# SIMM800C-STM32F103C8T6.net
KiCad netlist of a schematic drawn in Altium Designer
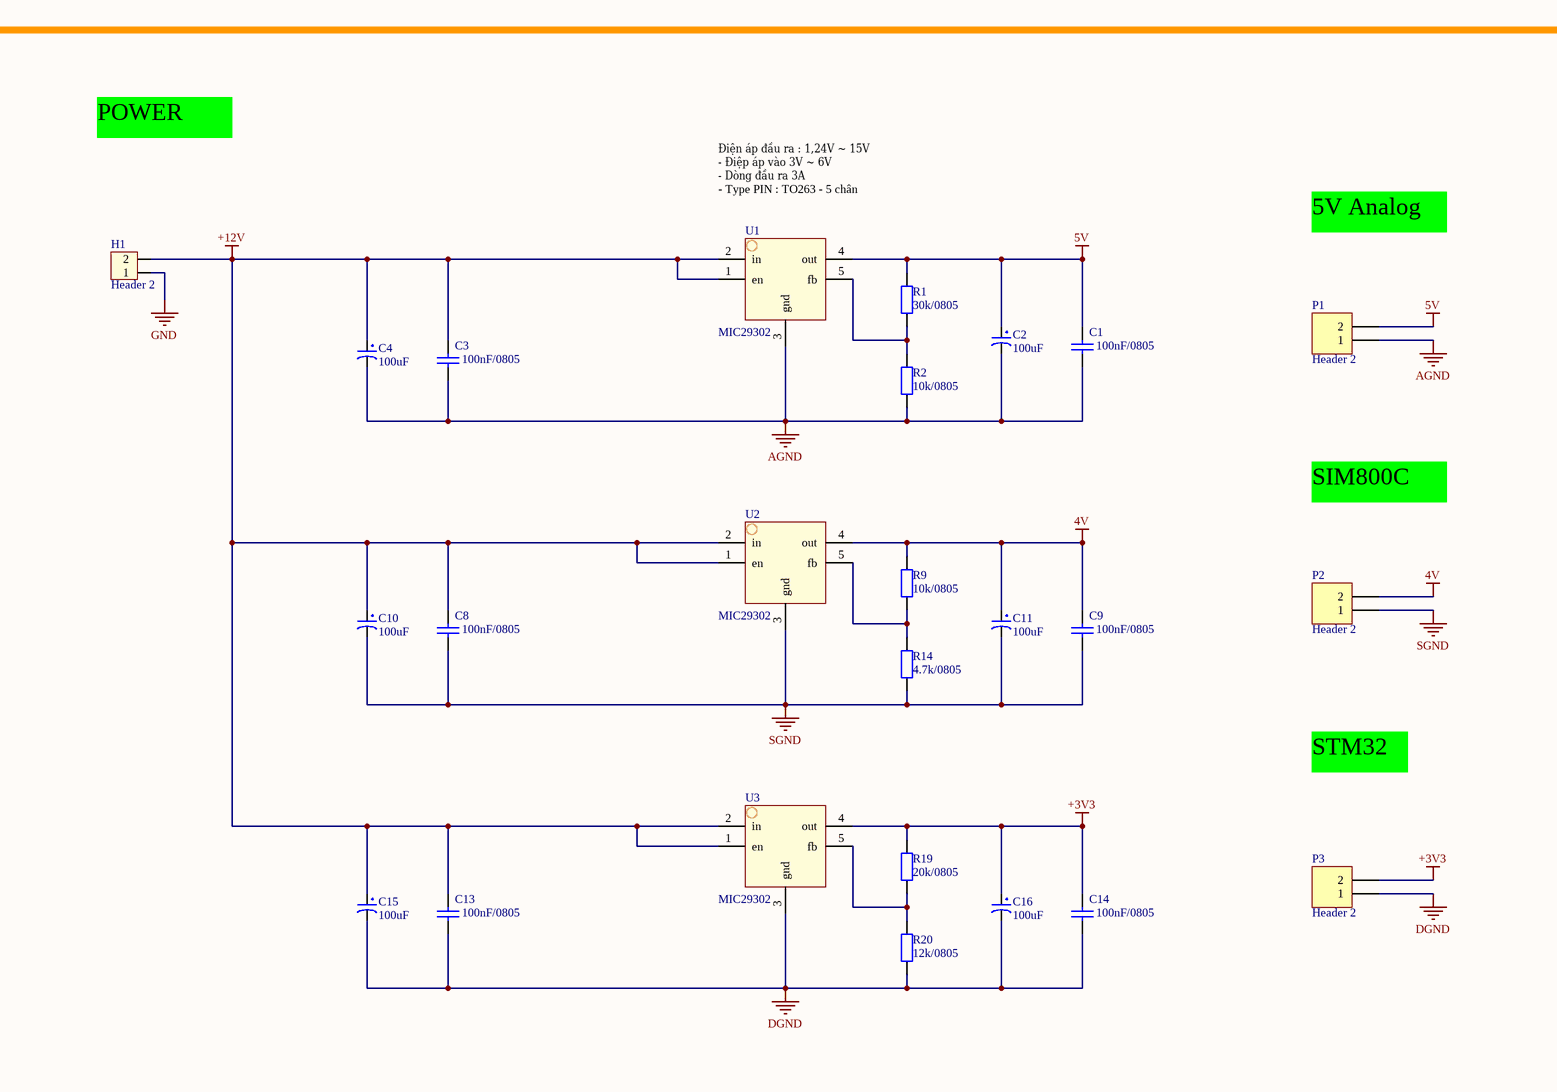
[diagram p0: SIMM800C-STM32F103C8T6.SchDoc, top left]
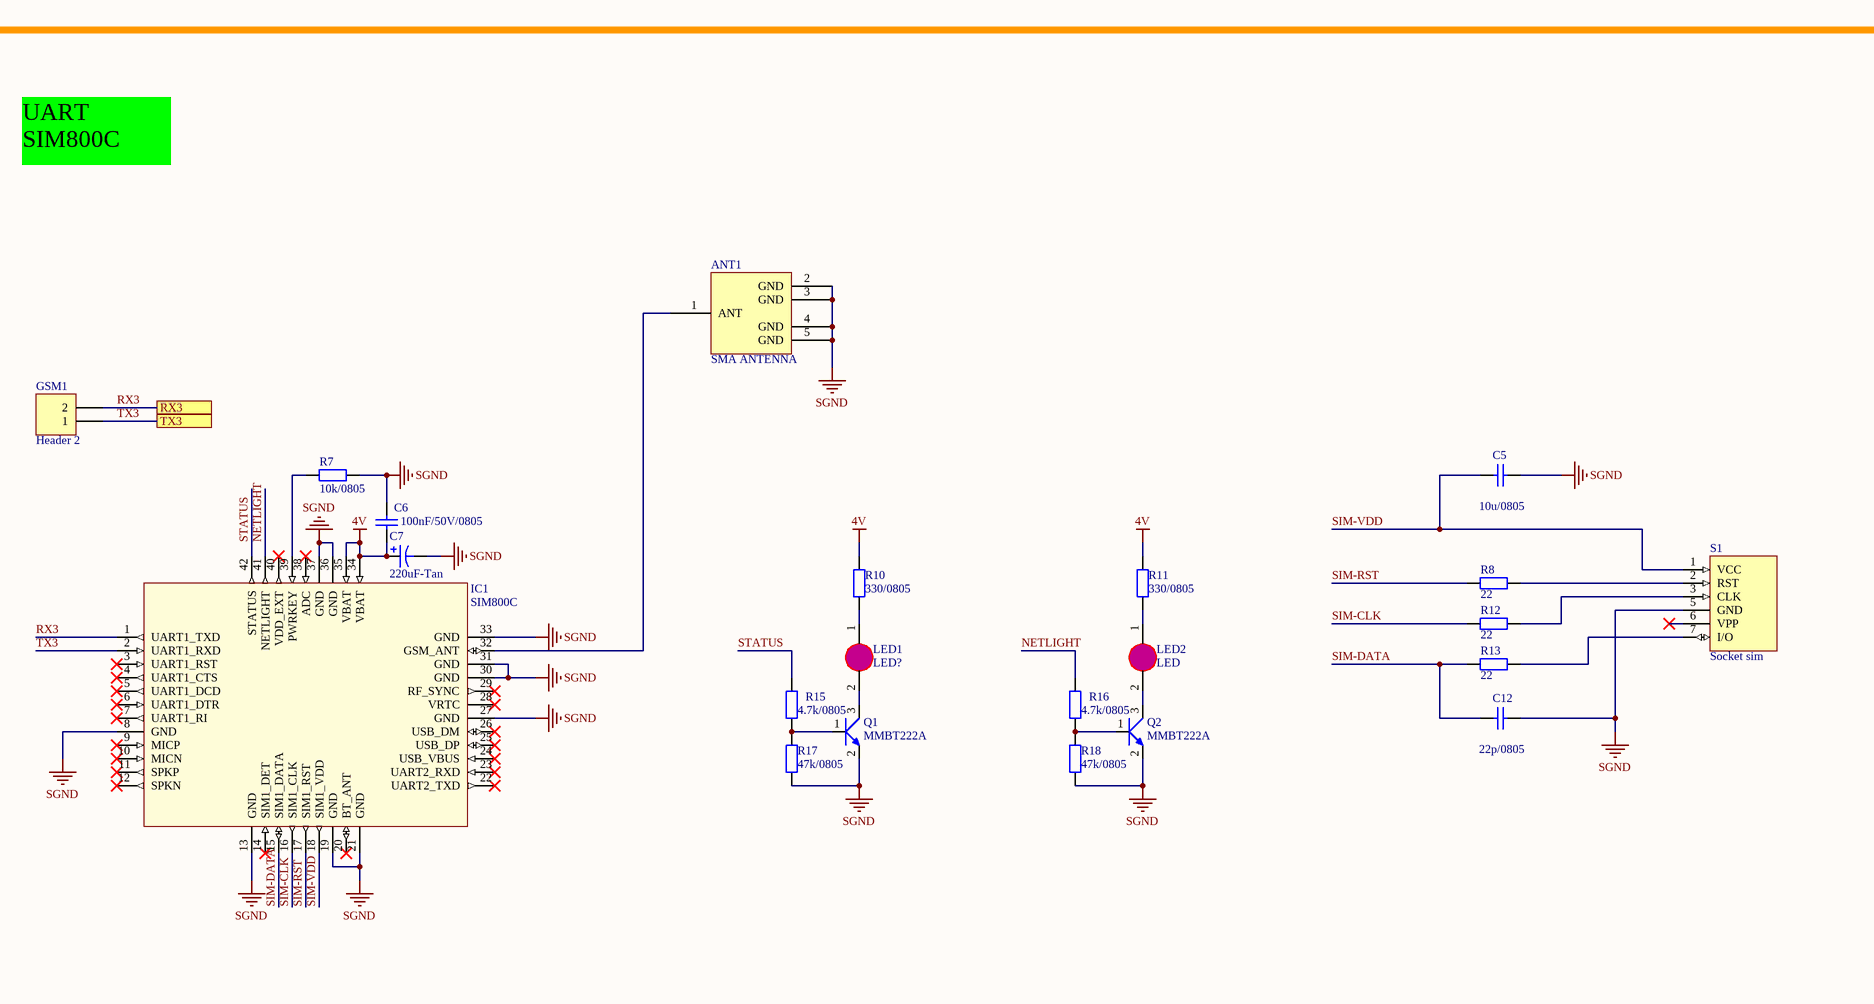
[diagram p1: SIMM800C-STM32F103C8T6.SchDoc, top right]
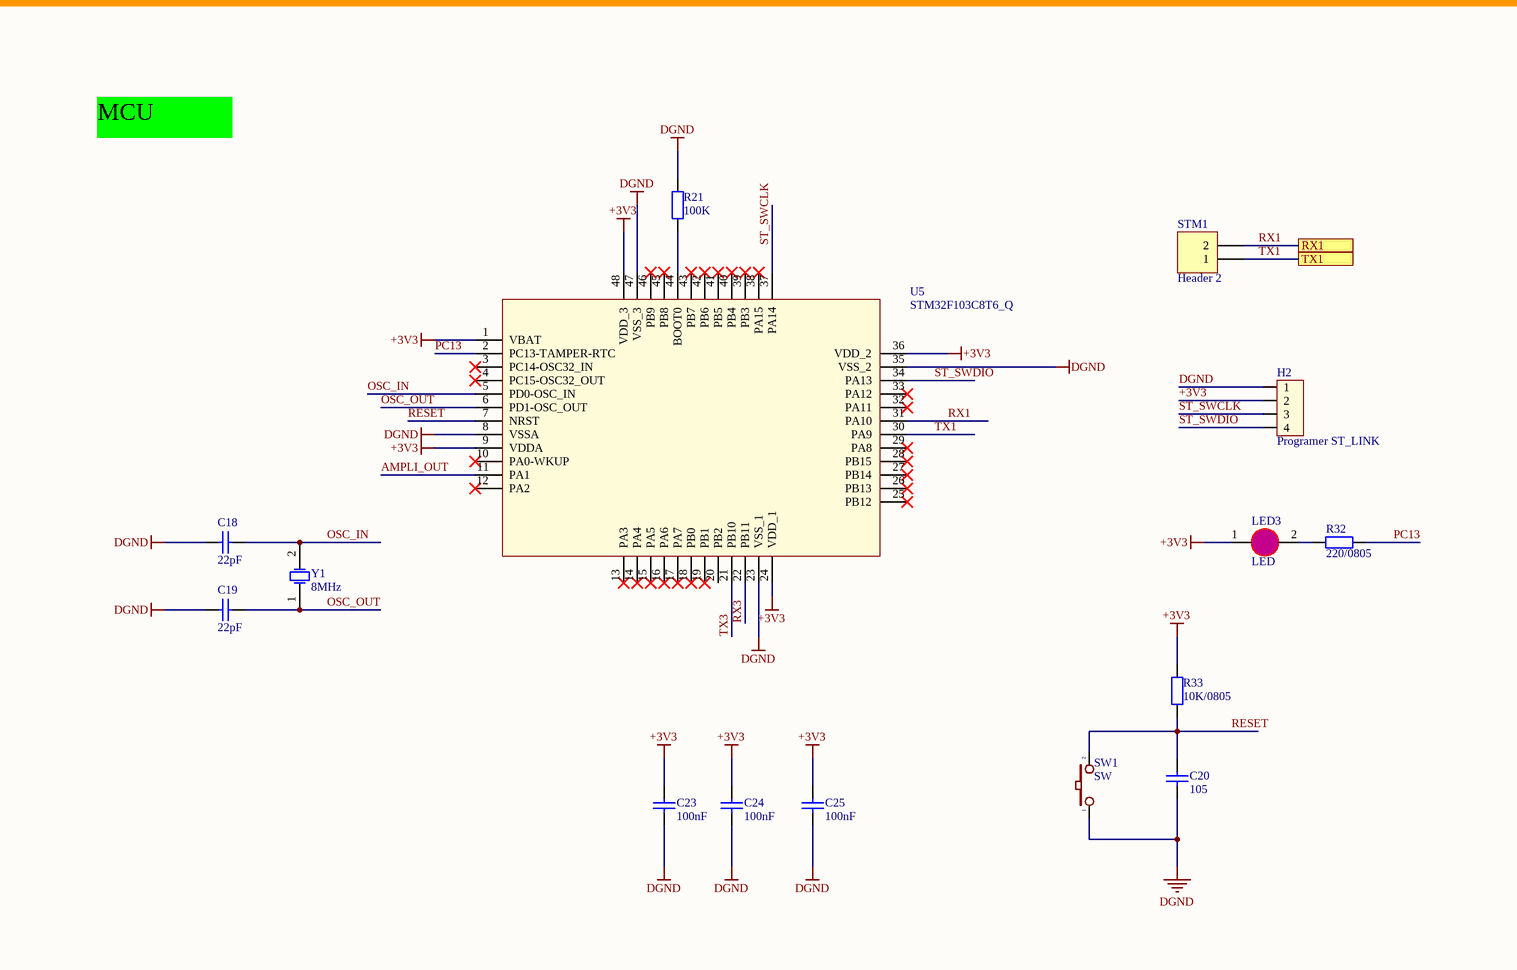
[diagram p2: SIMM800C-STM32F103C8T6.SchDoc, bottom left]
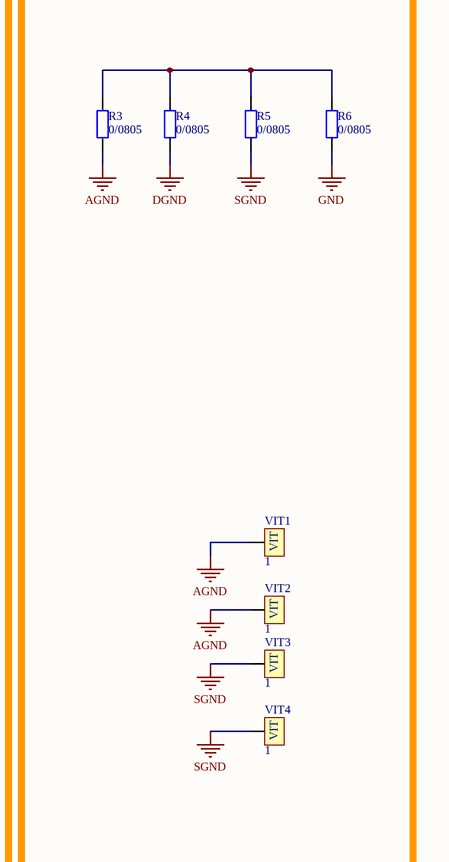
[diagram p3: SIMM800C-STM32F103C8T6.SchDoc, bottom right]

(export (version "E")
  (design (tool "Eeschema 10.0.6"))
  (components
    (comp (ref "ANT1")
      (value "SMA ANTENNA")
      (footprint "du an mau 1:ANT-SMA-ST-F")
      (libsource (lib "Air_System_lib") (part "SMA ANTENNA"))
    )
    (comp (ref "C1")
      (value "100nF/0805")
      (footprint "C0805-2012")
      (description "100nF/50V/0805")
      (fields (field (name "PUBLISHER") "Altium Limited"))
      (libsource (lib "NBBLib 14-03-2012") (part "CapSMD"))
    )
    (comp (ref "C2")
      (value "100uF")
      (footprint "CAP_TANTA_10UF_35V")
      (description "Cap 100uF/35V - 470uF/16V")
      (libsource (lib "lpson") (part "CP3"))
    )
    (comp (ref "C3")
      (value "100nF/0805")
      (footprint "C0805-2012")
      (description "100nF/50V/0805")
      (fields (field (name "PUBLISHER") "Altium Limited"))
      (libsource (lib "NBBLib 14-03-2012") (part "CapSMD"))
    )
    (comp (ref "C4")
      (value "100uF")
      (footprint "CAP_TANTA_10UF_35V")
      (description "Cap 100uF/35V - 470uF/16V")
      (libsource (lib "lpson") (part "CP3"))
    )
    (comp (ref "C5")
      (value "10u/0805")
      (footprint "C0805-2012")
      (description "Capacitor")
      (fields (field (name "PUBLISHER") "Altium Limited"))
      (libsource (lib "NBBLib 14-03-2012") (part "CapSMD"))
    )
    (comp (ref "C6")
      (value "100nF/50V/0805")
      (footprint "C0805-2012")
      (fields (field (name "PUBLISHER") "Altium Limited"))
      (libsource (lib "NBBLib 14-03-2012") (part "CapSMD"))
    )
    (comp (ref "C7")
      (value "220uF-Tan")
      (footprint "CAP_TANTA_10UF_35V")
      (libsource (lib "Air_System_lib") (part "CAP1210-Tan"))
    )
    (comp (ref "C8")
      (value "100nF/0805")
      (footprint "C0805-2012")
      (description "100nF/50V/0805")
      (fields (field (name "PUBLISHER") "Altium Limited"))
      (libsource (lib "NBBLib 14-03-2012") (part "CapSMD"))
    )
    (comp (ref "C9")
      (value "100nF/0805")
      (footprint "C0805-2012")
      (description "100nF/50V/0805")
      (fields (field (name "PUBLISHER") "Altium Limited"))
      (libsource (lib "NBBLib 14-03-2012") (part "CapSMD"))
    )
    (comp (ref "C10")
      (value "100uF")
      (footprint "CAP_TANTA_10UF_35V")
      (description "Cap 100uF/35V - 470uF/16V")
      (libsource (lib "lpson") (part "CP3"))
    )
    (comp (ref "C11")
      (value "100uF")
      (footprint "CAP_TANTA_10UF_35V")
      (description "Cap 100uF/35V - 470uF/16V")
      (libsource (lib "lpson") (part "CP3"))
    )
    (comp (ref "C12")
      (value "22p/0805")
      (footprint "C0805-2012")
      (description "Capacitor")
      (fields (field (name "PUBLISHER") "Altium Limited"))
      (libsource (lib "NBBLib 14-03-2012") (part "CapSMD"))
    )
    (comp (ref "C13")
      (value "100nF/0805")
      (footprint "C0805-2012")
      (description "100nF/50V/0805")
      (fields (field (name "PUBLISHER") "Altium Limited"))
      (libsource (lib "NBBLib 14-03-2012") (part "CapSMD"))
    )
    (comp (ref "C14")
      (value "100nF/0805")
      (footprint "C0805-2012")
      (description "100nF/50V/0805")
      (fields (field (name "PUBLISHER") "Altium Limited"))
      (libsource (lib "NBBLib 14-03-2012") (part "CapSMD"))
    )
    (comp (ref "C15")
      (value "100uF")
      (footprint "CAP_TANTA_10UF_35V")
      (description "Cap 100uF/35V - 470uF/16V")
      (libsource (lib "lpson") (part "CP3"))
    )
    (comp (ref "C16")
      (value "100uF")
      (footprint "CAP_TANTA_10UF_35V")
      (description "Cap 100uF/35V - 470uF/16V")
      (libsource (lib "lpson") (part "CP3"))
    )
    (comp (ref "C18")
      (value "22pF")
      (footprint "C0805-2012")
      (description "Capacitor")
      (fields (field (name "Comment") "Cap") (field (name "PUBLISHER") "Altium Limited"))
      (libsource (lib "STLINKv2DIYmơi") (part "Cap"))
    )
    (comp (ref "C19")
      (value "22pF")
      (footprint "C0805-2012")
      (description "Capacitor")
      (fields (field (name "Comment") "Cap") (field (name "PUBLISHER") "Altium Limited"))
      (libsource (lib "STLINKv2DIYmơi") (part "Cap"))
    )
    (comp (ref "C20")
      (value "105")
      (footprint "C0805-2012")
      (description "Capacitor")
      (fields (field (name "Comment") "Cap") (field (name "PUBLISHER") "Altium Limited"))
      (libsource (lib "STLINKv2DIYmơi") (part "Cap"))
    )
    (comp (ref "C23")
      (value "100nF")
      (footprint "C0805-2012")
      (description "Capacitor")
      (fields (field (name "Comment") "Cap") (field (name "PUBLISHER") "Altium Limited"))
      (libsource (lib "STLINKv2DIYmơi") (part "Cap"))
    )
    (comp (ref "C24")
      (value "100nF")
      (footprint "C0805-2012")
      (description "Capacitor")
      (fields (field (name "Comment") "Cap") (field (name "PUBLISHER") "Altium Limited"))
      (libsource (lib "STLINKv2DIYmơi") (part "Cap"))
    )
    (comp (ref "C25")
      (value "100nF")
      (footprint "C0805-2012")
      (description "Capacitor")
      (fields (field (name "Comment") "Cap") (field (name "PUBLISHER") "Altium Limited"))
      (libsource (lib "STLINKv2DIYmơi") (part "Cap"))
    )
    (comp (ref "GSM1")
      (value "Header 2")
      (footprint "Header_2")
      (description "Header, 2-Pin")
      (fields (field (name "PUBLISHER") "Altium Limited"))
      (libsource (lib "NBBLib 14-03-2012") (part "Header 2"))
    )
    (comp (ref "H1")
      (value "Header 2")
      (footprint "DOMINO2_GREEN")
      (description "Header 2 (Green)")
      (libsource (lib "lpson") (part "Hed2"))
    )
    (comp (ref "H2")
      (value "Programer ST_LINK")
      (footprint "Header_4")
      (description "Header 4 (Green)")
      (libsource (lib "lpson") (part "Hed4"))
    )
    (comp (ref "IC1")
      (value "SIM800C")
      (footprint "SIM800C")
      (description "SIM800C V1.00")
      (libsource (lib "LIEMTHANH_LIB") (part "SIM800C"))
    )
    (comp (ref "LED1")
      (value "LED?")
      (footprint "Led 0805R")
      (description "LED SMD 0805")
      (libsource (lib "NBBLib 14-03-2012") (part "LED0805"))
    )
    (comp (ref "LED2")
      (value "LED")
      (footprint "Led 0805R")
      (description "LED SMD 0805")
      (libsource (lib "NBBLib 14-03-2012") (part "LED0805"))
    )
    (comp (ref "LED3")
      (value "LED")
      (footprint "Led 0805G")
      (description "LED SMD 0805")
      (libsource (lib "NBBLib 14-03-2012") (part "LED0805"))
    )
    (comp (ref "P1")
      (value "Header 2")
      (footprint "Header_2")
      (description "Header, 2-Pin")
      (fields (field (name "PUBLISHER") "Altium Limited"))
      (libsource (lib "NBBLib 14-03-2012") (part "Header 2"))
    )
    (comp (ref "P2")
      (value "Header 2")
      (footprint "Header_2")
      (description "Header, 2-Pin")
      (fields (field (name "PUBLISHER") "Altium Limited"))
      (libsource (lib "NBBLib 14-03-2012") (part "Header 2"))
    )
    (comp (ref "P3")
      (value "Header 2")
      (footprint "Header_2")
      (description "Header, 2-Pin")
      (fields (field (name "PUBLISHER") "Altium Limited"))
      (libsource (lib "NBBLib 14-03-2012") (part "Header 2"))
    )
    (comp (ref "Q1")
      (value "MMBT222A")
      (footprint "MMBT2222A")
      (libsource (lib "Air_System_lib") (part "MMBT222A"))
    )
    (comp (ref "Q2")
      (value "MMBT222A")
      (footprint "MMBT2222A")
      (libsource (lib "Air_System_lib") (part "MMBT222A"))
    )
    (comp (ref "R1")
      (value "30k/0805")
      (footprint "RESC2012(0805)")
      (description "Resistor SMD 0805")
      (fields (field (name "PUBLISHER") "Altium Limited"))
      (libsource (lib "") (part "R0805_1"))
    )
    (comp (ref "R2")
      (value "10k/0805")
      (footprint "RESC2012(0805)")
      (description "Resistor SMD 0805")
      (fields (field (name "PUBLISHER") "Altium Limited"))
      (libsource (lib "") (part "R0805_1"))
    )
    (comp (ref "R3")
      (value "0/0805")
      (footprint "RESC2012(0805)")
      (description "Resistor SMD 0805")
      (fields (field (name "Comment") "R0805") (field (name "PUBLISHER") "Altium Limited"))
      (libsource (lib "") (part "R0805_1"))
    )
    (comp (ref "R4")
      (value "0/0805")
      (footprint "RESC2012(0805)")
      (description "Resistor SMD 0805")
      (fields (field (name "Comment") "R0805") (field (name "PUBLISHER") "Altium Limited"))
      (libsource (lib "") (part "R0805_1"))
    )
    (comp (ref "R5")
      (value "0/0805")
      (footprint "RESC2012(0805)")
      (description "Resistor SMD 0805")
      (fields (field (name "Comment") "R0805") (field (name "PUBLISHER") "Altium Limited"))
      (libsource (lib "") (part "R0805_1"))
    )
    (comp (ref "R6")
      (value "0/0805")
      (footprint "RESC2012(0805)")
      (description "Resistor SMD 0805")
      (fields (field (name "Comment") "R0805") (field (name "PUBLISHER") "Altium Limited"))
      (libsource (lib "") (part "R0805_1"))
    )
    (comp (ref "R7")
      (value "10k/0805")
      (footprint "RESC2012(0805)")
      (description "Resistor SMD 0805")
      (fields (field (name "PUBLISHER") "Altium Limited"))
      (libsource (lib "") (part "R0805_2"))
    )
    (comp (ref "R8")
      (value "22")
      (footprint "RESC2012(0805)")
      (description "Resistor SMD 0805")
      (fields (field (name "Comment") "R0805") (field (name "PUBLISHER") "Altium Limited"))
      (libsource (lib "") (part "R0805_2"))
    )
    (comp (ref "R9")
      (value "10k/0805")
      (footprint "RESC2012(0805)")
      (description "Resistor SMD 0805")
      (fields (field (name "PUBLISHER") "Altium Limited"))
      (libsource (lib "") (part "R0805_1"))
    )
    (comp (ref "R10")
      (value "330/0805")
      (footprint "RESC2012(0805)")
      (description "Resistor SMD 0805")
      (fields (field (name "Comment") "R0805") (field (name "PUBLISHER") "Altium Limited"))
      (libsource (lib "NBBLib 14-03-2012") (part "R0805"))
    )
    (comp (ref "R11")
      (value "330/0805")
      (footprint "RESC2012(0805)")
      (description "Resistor SMD 0805")
      (fields (field (name "Comment") "R0805") (field (name "PUBLISHER") "Altium Limited"))
      (libsource (lib "NBBLib 14-03-2012") (part "R0805"))
    )
    (comp (ref "R12")
      (value "22")
      (footprint "RESC2012(0805)")
      (description "Resistor SMD 0805")
      (fields (field (name "Comment") "R0805") (field (name "PUBLISHER") "Altium Limited"))
      (libsource (lib "") (part "R0805_2"))
    )
    (comp (ref "R13")
      (value "22")
      (footprint "RESC2012(0805)")
      (description "Resistor SMD 0805")
      (fields (field (name "Comment") "R0805") (field (name "PUBLISHER") "Altium Limited"))
      (libsource (lib "") (part "R0805_2"))
    )
    (comp (ref "R14")
      (value "4.7k/0805")
      (footprint "RESC2012(0805)")
      (description "Resistor SMD 0805")
      (fields (field (name "PUBLISHER") "Altium Limited"))
      (libsource (lib "") (part "R0805_1"))
    )
    (comp (ref "R15")
      (value "4.7k/0805")
      (footprint "RESC2012(0805)")
      (description "Resistor SMD 0805")
      (fields (field (name "Comment") "R0805") (field (name "PUBLISHER") "Altium Limited"))
      (libsource (lib "NBBLib 14-03-2012") (part "R0805"))
    )
    (comp (ref "R16")
      (value "4.7k/0805")
      (footprint "RESC2012(0805)")
      (description "Resistor SMD 0805")
      (fields (field (name "Comment") "R0805") (field (name "PUBLISHER") "Altium Limited"))
      (libsource (lib "NBBLib 14-03-2012") (part "R0805"))
    )
    (comp (ref "R17")
      (value "47k/0805")
      (footprint "RESC2012(0805)")
      (description "Resistor SMD 0805")
      (fields (field (name "Comment") "R0805") (field (name "PUBLISHER") "Altium Limited"))
      (libsource (lib "NBBLib 14-03-2012") (part "R0805"))
    )
    (comp (ref "R18")
      (value "47k/0805")
      (footprint "RESC2012(0805)")
      (description "Resistor SMD 0805")
      (fields (field (name "Comment") "R0805") (field (name "PUBLISHER") "Altium Limited"))
      (libsource (lib "NBBLib 14-03-2012") (part "R0805"))
    )
    (comp (ref "R19")
      (value "20k/0805")
      (footprint "RESC2012(0805)")
      (description "Resistor SMD 0805")
      (fields (field (name "PUBLISHER") "Altium Limited"))
      (libsource (lib "") (part "R0805_1"))
    )
    (comp (ref "R20")
      (value "12k/0805")
      (footprint "RESC2012(0805)")
      (description "Resistor SMD 0805")
      (fields (field (name "PUBLISHER") "Altium Limited"))
      (libsource (lib "") (part "R0805_1"))
    )
    (comp (ref "R21")
      (value "100K")
      (footprint "RESC2012(0805)")
      (description "Resistor")
      (fields (field (name "Comment") "Res2") (field (name "PUBLISHER") "Altium Limited"))
      (libsource (lib "STLINKv2DIYmơi") (part "Res2"))
    )
    (comp (ref "R32")
      (value "220/0805")
      (footprint "RESC2012(0805)")
      (description "Resistor SMD 0805")
      (fields (field (name "Comment") "R0805") (field (name "PUBLISHER") "Altium Limited"))
      (libsource (lib "") (part "R0805_2"))
    )
    (comp (ref "R33")
      (value "10K/0805")
      (footprint "RESC2012(0805)")
      (description "Resistor SMD 0805")
      (fields (field (name "Comment") "R0805") (field (name "PUBLISHER") "Altium Limited"))
      (libsource (lib "NBBLib 14-03-2012") (part "R0805"))
    )
    (comp (ref "S1")
      (value "Socket sim")
      (footprint "Card Sim")
      (libsource (lib "Air_System_lib") (part "Socket sim"))
    )
    (comp (ref "STM1")
      (value "Header 2")
      (footprint "Header_2")
      (description "Header, 2-Pin")
      (fields (field (name "PUBLISHER") "Altium Limited"))
      (libsource (lib "NBBLib 14-03-2012") (part "Header 2"))
    )
    (comp (ref "SW1")
      (value "SW")
      (footprint "BUTTON SMD EVQ - 2PIN")
      (description "Switch button 2 pin")
      (libsource (lib "lpson") (part "SW2"))
    )
    (comp (ref "U1")
      (value "MIC29302")
      (footprint "MIC29302")
      (description "SOC")
      (libsource (lib "PART2") (part "MIC29302"))
    )
    (comp (ref "U2")
      (value "MIC29302")
      (footprint "MIC29302")
      (description "SOC")
      (libsource (lib "PART2") (part "MIC29302"))
    )
    (comp (ref "U3")
      (value "MIC29302")
      (footprint "MIC29302")
      (description "SOC")
      (libsource (lib "PART2") (part "MIC29302"))
    )
    (comp (ref "U5")
      (value "STM32F103C8T6_Q")
      (footprint "STM32F103C8T6_Q")
      (libsource (lib "SCHSTM32F103C8T6_Q") (part "STM32F103C8T6_Q"))
    )
    (comp (ref "VIT1")
      (value "1")
      (footprint "VIT")
      (description "Oc Vit")
      (libsource (lib "lpson") (part "VIT"))
    )
    (comp (ref "VIT2")
      (value "1")
      (footprint "VIT")
      (description "Oc Vit")
      (libsource (lib "lpson") (part "VIT"))
    )
    (comp (ref "VIT3")
      (value "1")
      (footprint "VIT")
      (description "Oc Vit")
      (libsource (lib "lpson") (part "VIT"))
    )
    (comp (ref "VIT4")
      (value "1")
      (footprint "VIT")
      (description "Oc Vit")
      (libsource (lib "lpson") (part "VIT"))
    )
    (comp (ref "Y1")
      (value "8MHz")
      (footprint "CRYSTAL")
      (description "Crystal Oscillator")
      (fields (field (name "PUBLISHER") "Altium Limited"))
      (libsource (lib "STLINKv2DIYmơi") (part "XTAL"))
    )
  )
  (nets
    (net (code "1") (name "+3V3") (class "Default")
      (node (ref "C14") (pin "2") (pinfunction "2_2") (pintype "passive"))
      (node (ref "C16") (pin "1") (pinfunction "1_1") (pintype "passive"))
      (node (ref "C23") (pin "2") (pinfunction "2_2") (pintype "passive"))
      (node (ref "C24") (pin "2") (pinfunction "2_2") (pintype "passive"))
      (node (ref "C25") (pin "2") (pinfunction "2_2") (pintype "passive"))
      (node (ref "H2") (pin "2") (pinfunction "2_2") (pintype "passive"))
      (node (ref "LED3") (pin "1") (pinfunction "A_1") (pintype "passive"))
      (node (ref "P3") (pin "2") (pinfunction "2_2") (pintype "passive"))
      (node (ref "R19") (pin "2") (pinfunction "2_2") (pintype "passive"))
      (node (ref "R33") (pin "1") (pinfunction "1_1") (pintype "passive"))
      (node (ref "U3") (pin "4") (pinfunction "out_4") (pintype "passive"))
      (node (ref "U5") (pin "1") (pinfunction "VBAT_1") (pintype "passive"))
      (node (ref "U5") (pin "24") (pinfunction "VDD_1_24") (pintype "passive"))
      (node (ref "U5") (pin "36") (pinfunction "VDD_2_36") (pintype "passive"))
      (node (ref "U5") (pin "48") (pinfunction "VDD_3_48") (pintype "passive"))
      (node (ref "U5") (pin "9") (pinfunction "VDDA_9") (pintype "passive"))
    )
    (net (code "2") (name "+12V") (class "Default")
      (node (ref "C10") (pin "1") (pinfunction "1_1") (pintype "passive"))
      (node (ref "C13") (pin "2") (pinfunction "2_2") (pintype "passive"))
      (node (ref "C15") (pin "1") (pinfunction "1_1") (pintype "passive"))
      (node (ref "C3") (pin "2") (pinfunction "2_2") (pintype "passive"))
      (node (ref "C4") (pin "1") (pinfunction "1_1") (pintype "passive"))
      (node (ref "C8") (pin "2") (pinfunction "2_2") (pintype "passive"))
      (node (ref "H1") (pin "2") (pinfunction "2_2") (pintype "passive"))
      (node (ref "U1") (pin "1") (pinfunction "en_1") (pintype "passive"))
      (node (ref "U1") (pin "2") (pinfunction "in_2") (pintype "passive"))
      (node (ref "U2") (pin "1") (pinfunction "en_1") (pintype "passive"))
      (node (ref "U2") (pin "2") (pinfunction "in_2") (pintype "passive"))
      (node (ref "U3") (pin "1") (pinfunction "en_1") (pintype "passive"))
      (node (ref "U3") (pin "2") (pinfunction "in_2") (pintype "passive"))
    )
    (net (code "4") (name "/AMPLI_OUT") (class "Default")
      (node (ref "U5") (pin "11") (pinfunction "PA1_11") (pintype "passive"))
    )
    (net (code "5") (name "/NETLIGHT") (class "Default")
      (node (ref "IC1") (pin "41") (pinfunction "NETLIGHT_41") (pintype "output"))
      (node (ref "R16") (pin "1") (pinfunction "1_1") (pintype "passive"))
    )
    (net (code "6") (name "/OSC_IN") (class "Default")
      (node (ref "C18") (pin "2") (pinfunction "2_2") (pintype "passive"))
      (node (ref "U5") (pin "5") (pinfunction "PD0-OSC_IN_5") (pintype "passive"))
      (node (ref "Y1") (pin "2") (pinfunction "OSC2_2") (pintype "passive"))
    )
    (net (code "7") (name "/OSC_OUT") (class "Default")
      (node (ref "C19") (pin "2") (pinfunction "2_2") (pintype "passive"))
      (node (ref "U5") (pin "6") (pinfunction "PD1-OSC_OUT_6") (pintype "passive"))
      (node (ref "Y1") (pin "1") (pinfunction "OSC1_1") (pintype "passive"))
    )
    (net (code "8") (name "/PC13") (class "Default")
      (node (ref "R32") (pin "2") (pinfunction "2_2") (pintype "passive"))
      (node (ref "U5") (pin "2") (pinfunction "PC13-TAMPER-RTC_2") (pintype "passive"))
    )
    (net (code "9") (name "/RESET") (class "Default")
      (node (ref "C20") (pin "2") (pinfunction "2_2") (pintype "passive"))
      (node (ref "R33") (pin "2") (pinfunction "2_2") (pintype "passive"))
      (node (ref "SW1") (pin "2") (pinfunction "2_2") (pintype "passive"))
      (node (ref "U5") (pin "7") (pinfunction "NRST_7") (pintype "passive"))
    )
    (net (code "10") (name "/RX1") (class "Default")
      (node (ref "STM1") (pin "2") (pinfunction "2_2") (pintype "passive"))
      (node (ref "U5") (pin "31") (pinfunction "PA10_31") (pintype "passive"))
    )
    (net (code "11") (name "/RX3") (class "Default")
      (node (ref "GSM1") (pin "2") (pinfunction "2_2") (pintype "passive"))
      (node (ref "IC1") (pin "1") (pinfunction "UART1_TXD_1") (pintype "output"))
      (node (ref "U5") (pin "22") (pinfunction "PB11_22") (pintype "passive"))
    )
    (net (code "12") (name "/SIM-CLK") (class "Default")
      (node (ref "IC1") (pin "16") (pinfunction "SIM1_CLK_16") (pintype "output"))
      (node (ref "R12") (pin "1") (pinfunction "1_1") (pintype "passive"))
    )
    (net (code "13") (name "/SIM-DATA") (class "Default")
      (node (ref "C12") (pin "1") (pinfunction "1_1") (pintype "passive"))
      (node (ref "IC1") (pin "15") (pinfunction "SIM1_DATA_15") (pintype "bidirectional"))
      (node (ref "R13") (pin "1") (pinfunction "1_1") (pintype "passive"))
    )
    (net (code "14") (name "/SIM-RST") (class "Default")
      (node (ref "IC1") (pin "17") (pinfunction "SIM1_RST_17") (pintype "output"))
      (node (ref "R8") (pin "1") (pinfunction "1_1") (pintype "passive"))
    )
    (net (code "15") (name "/SIM-VDD") (class "Default")
      (node (ref "C5") (pin "1") (pinfunction "1_1") (pintype "passive"))
      (node (ref "IC1") (pin "18") (pinfunction "SIM1_VDD_18") (pintype "output"))
      (node (ref "S1") (pin "1") (pinfunction "VCC_1") (pintype "input"))
    )
    (net (code "16") (name "/STATUS") (class "Default")
      (node (ref "IC1") (pin "42") (pinfunction "STATUS_42") (pintype "output"))
      (node (ref "R15") (pin "1") (pinfunction "1_1") (pintype "passive"))
    )
    (net (code "17") (name "/ST_SWCLK") (class "Default")
      (node (ref "H2") (pin "3") (pinfunction "3_3") (pintype "passive"))
      (node (ref "U5") (pin "37") (pinfunction "PA14_37") (pintype "passive"))
    )
    (net (code "18") (name "/ST_SWDIO") (class "Default")
      (node (ref "H2") (pin "4") (pinfunction "4_4") (pintype "passive"))
      (node (ref "U5") (pin "34") (pinfunction "PA13_34") (pintype "passive"))
    )
    (net (code "19") (name "/TX1") (class "Default")
      (node (ref "STM1") (pin "1") (pinfunction "1_1") (pintype "passive"))
      (node (ref "U5") (pin "30") (pinfunction "PA9_30") (pintype "passive"))
    )
    (net (code "20") (name "/TX3") (class "Default")
      (node (ref "GSM1") (pin "1") (pinfunction "1_1") (pintype "passive"))
      (node (ref "IC1") (pin "2") (pinfunction "UART1_RXD_2") (pintype "input"))
      (node (ref "U5") (pin "21") (pinfunction "PB10_21") (pintype "passive"))
    )
    (net (code "21") (name "4V") (class "Default")
      (node (ref "C11") (pin "1") (pinfunction "1_1") (pintype "passive"))
      (node (ref "C6") (pin "1") (pinfunction "1_1") (pintype "passive"))
      (node (ref "C7") (pin "1") (pinfunction "1_1") (pintype "passive"))
      (node (ref "C9") (pin "2") (pinfunction "2_2") (pintype "passive"))
      (node (ref "IC1") (pin "34") (pinfunction "VBAT_34") (pintype "input"))
      (node (ref "IC1") (pin "35") (pinfunction "VBAT_35") (pintype "input"))
      (node (ref "P2") (pin "2") (pinfunction "2_2") (pintype "passive"))
      (node (ref "R10") (pin "1") (pinfunction "1_1") (pintype "passive"))
      (node (ref "R11") (pin "1") (pinfunction "1_1") (pintype "passive"))
      (node (ref "R9") (pin "2") (pinfunction "2_2") (pintype "passive"))
      (node (ref "U2") (pin "4") (pinfunction "out_4") (pintype "passive"))
    )
    (net (code "22") (name "5V") (class "Default")
      (node (ref "C1") (pin "2") (pinfunction "2_2") (pintype "passive"))
      (node (ref "C2") (pin "1") (pinfunction "1_1") (pintype "passive"))
      (node (ref "P1") (pin "2") (pinfunction "2_2") (pintype "passive"))
      (node (ref "R1") (pin "2") (pinfunction "2_2") (pintype "passive"))
      (node (ref "U1") (pin "4") (pinfunction "out_4") (pintype "passive"))
    )
    (net (code "23") (name "AGND") (class "Default")
      (node (ref "C1") (pin "1") (pinfunction "1_1") (pintype "passive"))
      (node (ref "C2") (pin "2") (pinfunction "2_2") (pintype "passive"))
      (node (ref "C3") (pin "1") (pinfunction "1_1") (pintype "passive"))
      (node (ref "C4") (pin "2") (pinfunction "2_2") (pintype "passive"))
      (node (ref "P1") (pin "1") (pinfunction "1_1") (pintype "passive"))
      (node (ref "R2") (pin "1") (pinfunction "1_1") (pintype "passive"))
      (node (ref "R3") (pin "1") (pinfunction "1_1") (pintype "passive"))
      (node (ref "U1") (pin "3") (pinfunction "gnd_3") (pintype "passive"))
      (node (ref "VIT1") (pin "VIT1") (pinfunction "1_VIT1") (pintype "passive"))
      (node (ref "VIT2") (pin "VIT1") (pinfunction "1_VIT1") (pintype "passive"))
    )
    (net (code "24") (name "DGND") (class "Default")
      (node (ref "C13") (pin "1") (pinfunction "1_1") (pintype "passive"))
      (node (ref "C14") (pin "1") (pinfunction "1_1") (pintype "passive"))
      (node (ref "C15") (pin "2") (pinfunction "2_2") (pintype "passive"))
      (node (ref "C16") (pin "2") (pinfunction "2_2") (pintype "passive"))
      (node (ref "C18") (pin "1") (pinfunction "1_1") (pintype "passive"))
      (node (ref "C19") (pin "1") (pinfunction "1_1") (pintype "passive"))
      (node (ref "C20") (pin "1") (pinfunction "1_1") (pintype "passive"))
      (node (ref "C23") (pin "1") (pinfunction "1_1") (pintype "passive"))
      (node (ref "C24") (pin "1") (pinfunction "1_1") (pintype "passive"))
      (node (ref "C25") (pin "1") (pinfunction "1_1") (pintype "passive"))
      (node (ref "H2") (pin "1") (pinfunction "1_1") (pintype "passive"))
      (node (ref "P3") (pin "1") (pinfunction "1_1") (pintype "passive"))
      (node (ref "R20") (pin "1") (pinfunction "1_1") (pintype "passive"))
      (node (ref "R21") (pin "2") (pinfunction "2_2") (pintype "passive"))
      (node (ref "R4") (pin "1") (pinfunction "1_1") (pintype "passive"))
      (node (ref "SW1") (pin "1") (pinfunction "1_1") (pintype "passive"))
      (node (ref "U3") (pin "3") (pinfunction "gnd_3") (pintype "passive"))
      (node (ref "U5") (pin "23") (pinfunction "VSS_1_23") (pintype "passive"))
      (node (ref "U5") (pin "35") (pinfunction "VSS_2_35") (pintype "passive"))
      (node (ref "U5") (pin "47") (pinfunction "VSS_3_47") (pintype "passive"))
      (node (ref "U5") (pin "8") (pinfunction "VSSA_8") (pintype "passive"))
    )
    (net (code "25") (name "GND") (class "Default")
      (node (ref "H1") (pin "1") (pinfunction "1_1") (pintype "passive"))
      (node (ref "R6") (pin "1") (pinfunction "1_1") (pintype "passive"))
    )
    (net (code "26") (name "Net-(ANT1-ANT)") (class "Default")
      (node (ref "ANT1") (pin "1") (pinfunction "ANT_1") (pintype "passive"))
      (node (ref "IC1") (pin "32") (pinfunction "GSM_ANT_32") (pintype "bidirectional"))
    )
    (net (code "27") (name "Net-(IC1-PWRKEY)") (class "Default")
      (node (ref "IC1") (pin "39") (pinfunction "PWRKEY_39") (pintype "input"))
      (node (ref "R7") (pin "1") (pinfunction "1_1") (pintype "passive"))
    )
    (net (code "28") (name "Net-(LED1-A)") (class "Default")
      (node (ref "LED1") (pin "1") (pinfunction "A_1") (pintype "passive"))
      (node (ref "R10") (pin "2") (pinfunction "2_2") (pintype "passive"))
    )
    (net (code "29") (name "Net-(LED1-K)") (class "Default")
      (node (ref "LED1") (pin "2") (pinfunction "K_2") (pintype "passive"))
      (node (ref "Q1") (pin "3") (pinfunction "3_3") (pintype "passive"))
    )
    (net (code "30") (name "Net-(LED2-A)") (class "Default")
      (node (ref "LED2") (pin "1") (pinfunction "A_1") (pintype "passive"))
      (node (ref "R11") (pin "2") (pinfunction "2_2") (pintype "passive"))
    )
    (net (code "31") (name "Net-(LED2-K)") (class "Default")
      (node (ref "LED2") (pin "2") (pinfunction "K_2") (pintype "passive"))
      (node (ref "Q2") (pin "3") (pinfunction "3_3") (pintype "passive"))
    )
    (net (code "32") (name "Net-(LED3-K)") (class "Default")
      (node (ref "LED3") (pin "2") (pinfunction "K_2") (pintype "passive"))
      (node (ref "R32") (pin "1") (pinfunction "1_1") (pintype "passive"))
    )
    (net (code "33") (name "Net-(Q1-Pad1)") (class "Default")
      (node (ref "Q1") (pin "1") (pinfunction "1_1") (pintype "passive"))
      (node (ref "R15") (pin "2") (pinfunction "2_2") (pintype "passive"))
      (node (ref "R17") (pin "1") (pinfunction "1_1") (pintype "passive"))
    )
    (net (code "34") (name "Net-(Q2-Pad1)") (class "Default")
      (node (ref "Q2") (pin "1") (pinfunction "1_1") (pintype "passive"))
      (node (ref "R16") (pin "2") (pinfunction "2_2") (pintype "passive"))
      (node (ref "R18") (pin "1") (pinfunction "1_1") (pintype "passive"))
    )
    (net (code "35") (name "Net-(R3-Pad2)") (class "Default")
      (node (ref "R3") (pin "2") (pinfunction "2_2") (pintype "passive"))
      (node (ref "R4") (pin "2") (pinfunction "2_2") (pintype "passive"))
      (node (ref "R5") (pin "2") (pinfunction "2_2") (pintype "passive"))
      (node (ref "R6") (pin "2") (pinfunction "2_2") (pintype "passive"))
    )
    (net (code "36") (name "Net-(S1-CLK)") (class "Default")
      (node (ref "R12") (pin "2") (pinfunction "2_2") (pintype "passive"))
      (node (ref "S1") (pin "3") (pinfunction "CLK_3") (pintype "input"))
    )
    (net (code "37") (name "Net-(S1-I{slash}O)") (class "Default")
      (node (ref "R13") (pin "2") (pinfunction "2_2") (pintype "passive"))
      (node (ref "S1") (pin "7") (pinfunction "I/O_7") (pintype "bidirectional"))
    )
    (net (code "38") (name "Net-(S1-RST)") (class "Default")
      (node (ref "R8") (pin "2") (pinfunction "2_2") (pintype "passive"))
      (node (ref "S1") (pin "2") (pinfunction "RST_2") (pintype "input"))
    )
    (net (code "39") (name "Net-(U1-fb)") (class "Default")
      (node (ref "R1") (pin "1") (pinfunction "1_1") (pintype "passive"))
      (node (ref "R2") (pin "2") (pinfunction "2_2") (pintype "passive"))
      (node (ref "U1") (pin "5") (pinfunction "fb_5") (pintype "passive"))
    )
    (net (code "40") (name "Net-(U2-fb)") (class "Default")
      (node (ref "R14") (pin "2") (pinfunction "2_2") (pintype "passive"))
      (node (ref "R9") (pin "1") (pinfunction "1_1") (pintype "passive"))
      (node (ref "U2") (pin "5") (pinfunction "fb_5") (pintype "passive"))
    )
    (net (code "41") (name "Net-(U3-fb)") (class "Default")
      (node (ref "R19") (pin "1") (pinfunction "1_1") (pintype "passive"))
      (node (ref "R20") (pin "2") (pinfunction "2_2") (pintype "passive"))
      (node (ref "U3") (pin "5") (pinfunction "fb_5") (pintype "passive"))
    )
    (net (code "42") (name "Net-(U5-BOOT0)") (class "Default")
      (node (ref "R21") (pin "1") (pinfunction "1_1") (pintype "passive"))
      (node (ref "U5") (pin "44") (pinfunction "BOOT0_44") (pintype "passive"))
    )
    (net (code "43") (name "SGND") (class "Default")
      (node (ref "ANT1") (pin "2") (pinfunction "GND_2") (pintype "passive"))
      (node (ref "ANT1") (pin "3") (pinfunction "GND_3") (pintype "passive"))
      (node (ref "ANT1") (pin "4") (pinfunction "GND_4") (pintype "passive"))
      (node (ref "ANT1") (pin "5") (pinfunction "GND_5") (pintype "passive"))
      (node (ref "C10") (pin "2") (pinfunction "2_2") (pintype "passive"))
      (node (ref "C11") (pin "2") (pinfunction "2_2") (pintype "passive"))
      (node (ref "C12") (pin "2") (pinfunction "2_2") (pintype "passive"))
      (node (ref "C5") (pin "2") (pinfunction "2_2") (pintype "passive"))
      (node (ref "C6") (pin "2") (pinfunction "2_2") (pintype "passive"))
      (node (ref "C7") (pin "2") (pinfunction "2_2") (pintype "passive"))
      (node (ref "C8") (pin "1") (pinfunction "1_1") (pintype "passive"))
      (node (ref "C9") (pin "1") (pinfunction "1_1") (pintype "passive"))
      (node (ref "IC1") (pin "13") (pinfunction "GND_13") (pintype "power_in"))
      (node (ref "IC1") (pin "19") (pinfunction "GND_19") (pintype "power_in"))
      (node (ref "IC1") (pin "21") (pinfunction "GND_21") (pintype "power_in"))
      (node (ref "IC1") (pin "27") (pinfunction "GND_27") (pintype "power_in"))
      (node (ref "IC1") (pin "30") (pinfunction "GND_30") (pintype "power_in"))
      (node (ref "IC1") (pin "31") (pinfunction "GND_31") (pintype "power_in"))
      (node (ref "IC1") (pin "33") (pinfunction "GND_33") (pintype "power_in"))
      (node (ref "IC1") (pin "36") (pinfunction "GND_36") (pintype "power_in"))
      (node (ref "IC1") (pin "37") (pinfunction "GND_37") (pintype "power_in"))
      (node (ref "IC1") (pin "8") (pinfunction "GND_8") (pintype "power_in"))
      (node (ref "P2") (pin "1") (pinfunction "1_1") (pintype "passive"))
      (node (ref "Q1") (pin "2") (pinfunction "2_2") (pintype "passive"))
      (node (ref "Q2") (pin "2") (pinfunction "2_2") (pintype "passive"))
      (node (ref "R14") (pin "1") (pinfunction "1_1") (pintype "passive"))
      (node (ref "R17") (pin "2") (pinfunction "2_2") (pintype "passive"))
      (node (ref "R18") (pin "2") (pinfunction "2_2") (pintype "passive"))
      (node (ref "R5") (pin "1") (pinfunction "1_1") (pintype "passive"))
      (node (ref "R7") (pin "2") (pinfunction "2_2") (pintype "passive"))
      (node (ref "S1") (pin "5") (pinfunction "GND_5") (pintype "passive"))
      (node (ref "U2") (pin "3") (pinfunction "gnd_3") (pintype "passive"))
      (node (ref "VIT3") (pin "VIT1") (pinfunction "1_VIT1") (pintype "passive"))
      (node (ref "VIT4") (pin "VIT1") (pinfunction "1_VIT1") (pintype "passive"))
    )
    (net (code "44") (name "unconnected-(IC1-ADC-Pad38)") (class "Default")
      (node (ref "IC1") (pin "38") (pinfunction "ADC_38") (pintype "input+no_connect"))
    )
    (net (code "45") (name "unconnected-(IC1-BT_ANT-Pad20)") (class "Default")
      (node (ref "IC1") (pin "20") (pinfunction "BT_ANT_20") (pintype "bidirectional+no_connect"))
    )
    (net (code "46") (name "unconnected-(IC1-MICN-Pad10)") (class "Default")
      (node (ref "IC1") (pin "10") (pinfunction "MICN_10") (pintype "input+no_connect"))
    )
    (net (code "47") (name "unconnected-(IC1-MICP-Pad9)") (class "Default")
      (node (ref "IC1") (pin "9") (pinfunction "MICP_9") (pintype "input+no_connect"))
    )
    (net (code "48") (name "unconnected-(IC1-RF_SYNC-Pad29)") (class "Default")
      (node (ref "IC1") (pin "29") (pinfunction "RF_SYNC_29") (pintype "output+no_connect"))
    )
    (net (code "49") (name "unconnected-(IC1-SIM1_DET-Pad14)") (class "Default")
      (node (ref "IC1") (pin "14") (pinfunction "SIM1_DET_14") (pintype "input+no_connect"))
    )
    (net (code "50") (name "unconnected-(IC1-SPKN-Pad12)") (class "Default")
      (node (ref "IC1") (pin "12") (pinfunction "SPKN_12") (pintype "output+no_connect"))
    )
    (net (code "51") (name "unconnected-(IC1-SPKP-Pad11)") (class "Default")
      (node (ref "IC1") (pin "11") (pinfunction "SPKP_11") (pintype "output+no_connect"))
    )
    (net (code "52") (name "unconnected-(IC1-UART1_CTS-Pad4)") (class "Default")
      (node (ref "IC1") (pin "4") (pinfunction "UART1_CTS_4") (pintype "output+no_connect"))
    )
    (net (code "53") (name "unconnected-(IC1-UART1_DCD-Pad5)") (class "Default")
      (node (ref "IC1") (pin "5") (pinfunction "UART1_DCD_5") (pintype "output+no_connect"))
    )
    (net (code "54") (name "unconnected-(IC1-UART1_DTR-Pad6)") (class "Default")
      (node (ref "IC1") (pin "6") (pinfunction "UART1_DTR_6") (pintype "input+no_connect"))
    )
    (net (code "55") (name "unconnected-(IC1-UART1_RI-Pad7)") (class "Default")
      (node (ref "IC1") (pin "7") (pinfunction "UART1_RI_7") (pintype "output+no_connect"))
    )
    (net (code "56") (name "unconnected-(IC1-UART1_RST-Pad3)") (class "Default")
      (node (ref "IC1") (pin "3") (pinfunction "UART1_RST_3") (pintype "input+no_connect"))
    )
    (net (code "57") (name "unconnected-(IC1-UART2_RXD-Pad23)") (class "Default")
      (node (ref "IC1") (pin "23") (pinfunction "UART2_RXD_23") (pintype "input+no_connect"))
    )
    (net (code "58") (name "unconnected-(IC1-UART2_TXD-Pad22)") (class "Default")
      (node (ref "IC1") (pin "22") (pinfunction "UART2_TXD_22") (pintype "output+no_connect"))
    )
    (net (code "59") (name "unconnected-(IC1-USB_DM-Pad26)") (class "Default")
      (node (ref "IC1") (pin "26") (pinfunction "USB_DM_26") (pintype "bidirectional+no_connect"))
    )
    (net (code "60") (name "unconnected-(IC1-USB_DP-Pad25)") (class "Default")
      (node (ref "IC1") (pin "25") (pinfunction "USB_DP_25") (pintype "bidirectional+no_connect"))
    )
    (net (code "61") (name "unconnected-(IC1-USB_VBUS-Pad24)") (class "Default")
      (node (ref "IC1") (pin "24") (pinfunction "USB_VBUS_24") (pintype "input+no_connect"))
    )
    (net (code "62") (name "unconnected-(IC1-VDD_EXT-Pad40)") (class "Default")
      (node (ref "IC1") (pin "40") (pinfunction "VDD_EXT_40") (pintype "output+no_connect"))
    )
    (net (code "63") (name "unconnected-(IC1-VRTC-Pad28)") (class "Default")
      (node (ref "IC1") (pin "28") (pinfunction "VRTC_28") (pintype "passive+no_connect"))
    )
    (net (code "64") (name "unconnected-(S1-VPP-Pad6)") (class "Default")
      (node (ref "S1") (pin "6") (pinfunction "VPP_6") (pintype "passive+no_connect"))
    )
    (net (code "65") (name "unconnected-(U5-PA0-WKUP-Pad10)") (class "Default")
      (node (ref "U5") (pin "10") (pinfunction "PA0-WKUP_10") (pintype "passive+no_connect"))
    )
    (net (code "66") (name "unconnected-(U5-PA2-Pad12)") (class "Default")
      (node (ref "U5") (pin "12") (pinfunction "PA2_12") (pintype "passive+no_connect"))
    )
    (net (code "67") (name "unconnected-(U5-PA3-Pad13)") (class "Default")
      (node (ref "U5") (pin "13") (pinfunction "PA3_13") (pintype "passive+no_connect"))
    )
    (net (code "68") (name "unconnected-(U5-PA4-Pad14)") (class "Default")
      (node (ref "U5") (pin "14") (pinfunction "PA4_14") (pintype "passive+no_connect"))
    )
    (net (code "69") (name "unconnected-(U5-PA5-Pad15)") (class "Default")
      (node (ref "U5") (pin "15") (pinfunction "PA5_15") (pintype "passive+no_connect"))
    )
    (net (code "70") (name "unconnected-(U5-PA6-Pad16)") (class "Default")
      (node (ref "U5") (pin "16") (pinfunction "PA6_16") (pintype "passive+no_connect"))
    )
    (net (code "71") (name "unconnected-(U5-PA7-Pad17)") (class "Default")
      (node (ref "U5") (pin "17") (pinfunction "PA7_17") (pintype "passive+no_connect"))
    )
    (net (code "72") (name "unconnected-(U5-PA8-Pad29)") (class "Default")
      (node (ref "U5") (pin "29") (pinfunction "PA8_29") (pintype "passive+no_connect"))
    )
    (net (code "73") (name "unconnected-(U5-PA11-Pad32)") (class "Default")
      (node (ref "U5") (pin "32") (pinfunction "PA11_32") (pintype "passive+no_connect"))
    )
    (net (code "74") (name "unconnected-(U5-PA12-Pad33)") (class "Default")
      (node (ref "U5") (pin "33") (pinfunction "PA12_33") (pintype "passive+no_connect"))
    )
    (net (code "75") (name "unconnected-(U5-PA15-Pad38)") (class "Default")
      (node (ref "U5") (pin "38") (pinfunction "PA15_38") (pintype "passive+no_connect"))
    )
    (net (code "76") (name "unconnected-(U5-PB0-Pad18)") (class "Default")
      (node (ref "U5") (pin "18") (pinfunction "PB0_18") (pintype "passive+no_connect"))
    )
    (net (code "77") (name "unconnected-(U5-PB1-Pad19)") (class "Default")
      (node (ref "U5") (pin "19") (pinfunction "PB1_19") (pintype "passive+no_connect"))
    )
    (net (code "78") (name "unconnected-(U5-PB2-Pad20)") (class "Default")
      (node (ref "U5") (pin "20") (pinfunction "PB2_20") (pintype "passive"))
    )
    (net (code "79") (name "unconnected-(U5-PB3-Pad39)") (class "Default")
      (node (ref "U5") (pin "39") (pinfunction "PB3_39") (pintype "passive+no_connect"))
    )
    (net (code "80") (name "unconnected-(U5-PB4-Pad40)") (class "Default")
      (node (ref "U5") (pin "40") (pinfunction "PB4_40") (pintype "passive+no_connect"))
    )
    (net (code "81") (name "unconnected-(U5-PB5-Pad41)") (class "Default")
      (node (ref "U5") (pin "41") (pinfunction "PB5_41") (pintype "passive+no_connect"))
    )
    (net (code "82") (name "unconnected-(U5-PB6-Pad42)") (class "Default")
      (node (ref "U5") (pin "42") (pinfunction "PB6_42") (pintype "passive+no_connect"))
    )
    (net (code "83") (name "unconnected-(U5-PB7-Pad43)") (class "Default")
      (node (ref "U5") (pin "43") (pinfunction "PB7_43") (pintype "passive+no_connect"))
    )
    (net (code "84") (name "unconnected-(U5-PB8-Pad45)") (class "Default")
      (node (ref "U5") (pin "45") (pinfunction "PB8_45") (pintype "passive+no_connect"))
    )
    (net (code "85") (name "unconnected-(U5-PB9-Pad46)") (class "Default")
      (node (ref "U5") (pin "46") (pinfunction "PB9_46") (pintype "passive+no_connect"))
    )
    (net (code "86") (name "unconnected-(U5-PB12-Pad25)") (class "Default")
      (node (ref "U5") (pin "25") (pinfunction "PB12_25") (pintype "passive+no_connect"))
    )
    (net (code "87") (name "unconnected-(U5-PB13-Pad26)") (class "Default")
      (node (ref "U5") (pin "26") (pinfunction "PB13_26") (pintype "passive+no_connect"))
    )
    (net (code "88") (name "unconnected-(U5-PB14-Pad27)") (class "Default")
      (node (ref "U5") (pin "27") (pinfunction "PB14_27") (pintype "passive+no_connect"))
    )
    (net (code "89") (name "unconnected-(U5-PB15-Pad28)") (class "Default")
      (node (ref "U5") (pin "28") (pinfunction "PB15_28") (pintype "passive+no_connect"))
    )
    (net (code "90") (name "unconnected-(U5-PC14-OSC32_IN-Pad3)") (class "Default")
      (node (ref "U5") (pin "3") (pinfunction "PC14-OSC32_IN_3") (pintype "passive+no_connect"))
    )
    (net (code "91") (name "unconnected-(U5-PC15-OSC32_OUT-Pad4)") (class "Default")
      (node (ref "U5") (pin "4") (pinfunction "PC15-OSC32_OUT_4") (pintype "passive+no_connect"))
    )
  )
)
